# P10_EX-Headers.net
KiCad netlist of a schematic drawn in Altium Designer
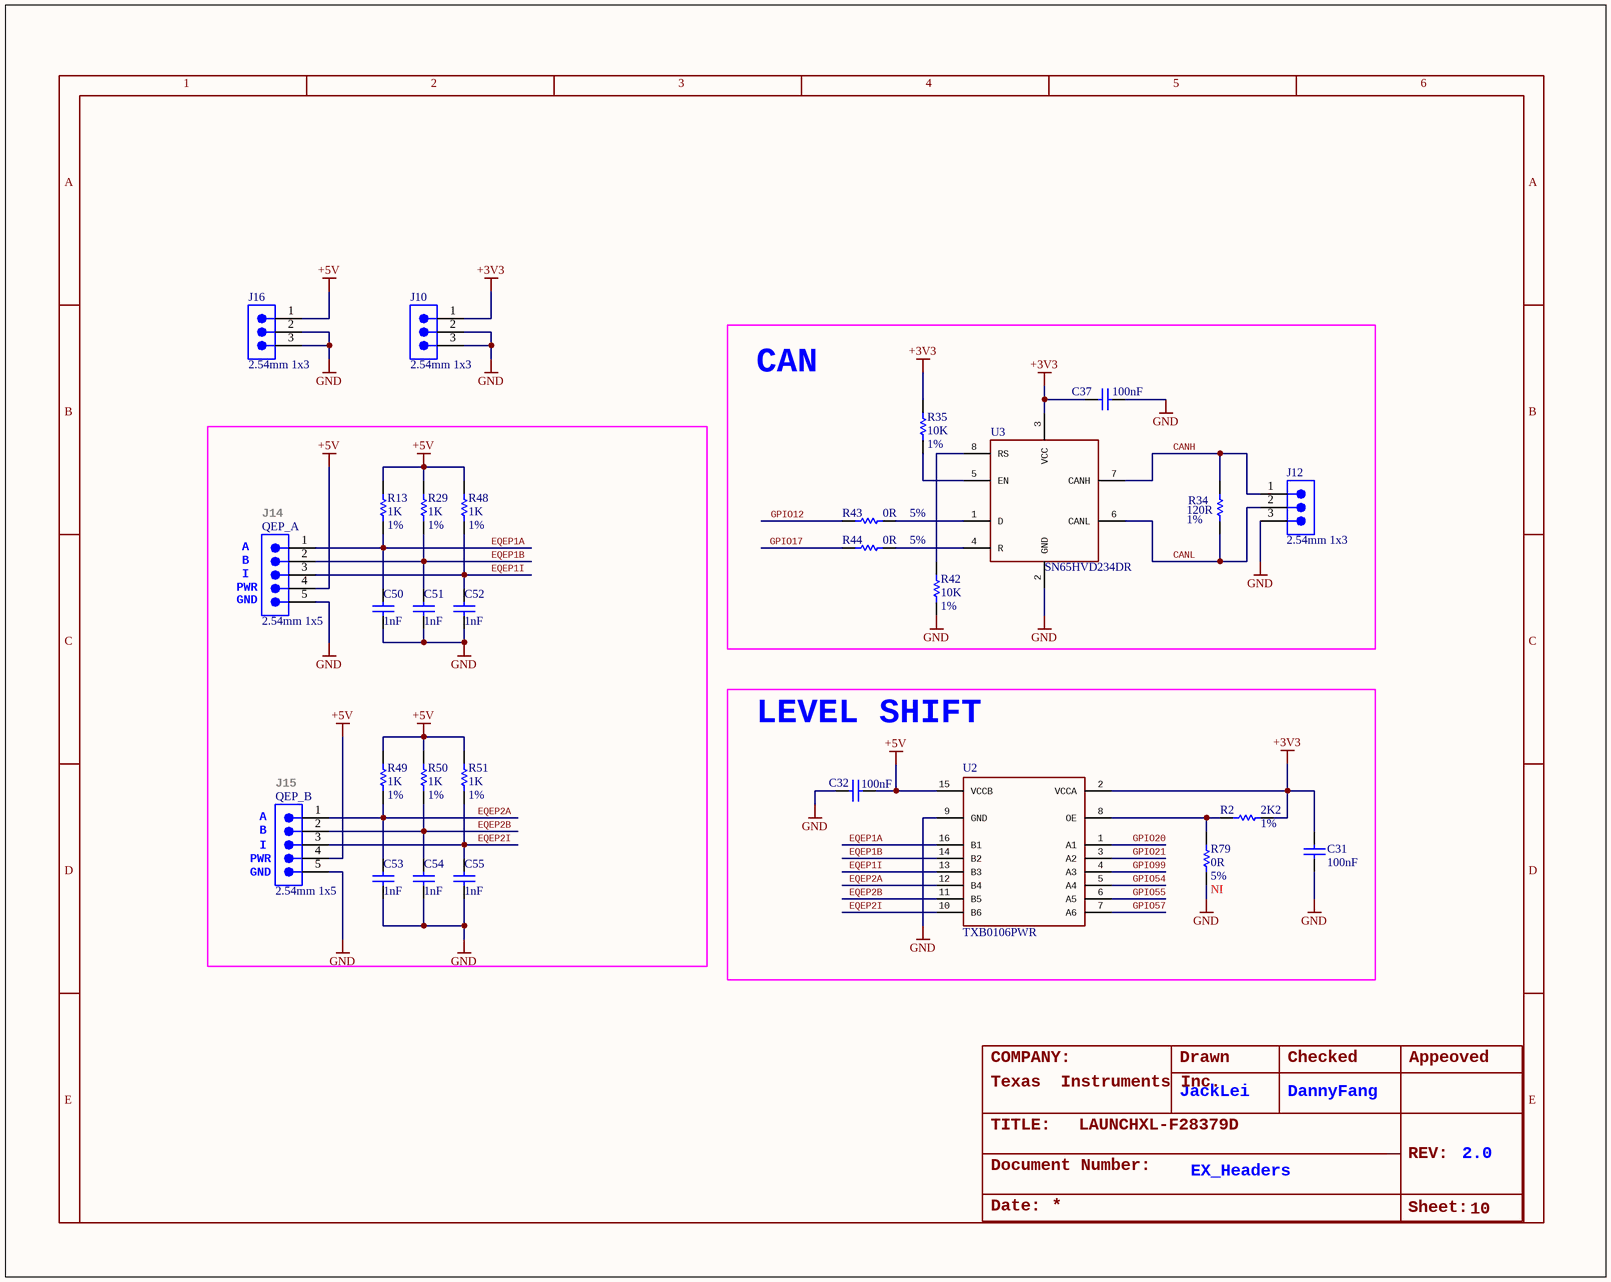
[diagram p0: P10_EX-Headers.SchDoc]

(export (version "E")
  (design (tool "Eeschema 10.0.6"))
  (components
    (comp (ref "C31")
      (value "100nF")
      (footprint "C0402")
      (description "CAP,100NF(0.1uf),+/-10%,X5R,10V,SMD0402")
      (fields
        (field (name "MANUFACTURER") "MURATA")
        (field (name "MANUFACTURER PART NUMBER") "GRM155R61A104KA01D")
      )
      (libsource (lib "Embest") (part "C"))
    )
    (comp (ref "C32")
      (value "100nF")
      (footprint "C0402")
      (description "CAP,100NF(0.1uf),+/-10%,X5R,10V,SMD0402")
      (fields
        (field (name "MANUFACTURER") "MURATA")
        (field (name "MANUFACTURER PART NUMBER") "GRM155R61A104KA01D")
      )
      (libsource (lib "Embest") (part "C"))
    )
    (comp (ref "C37")
      (value "100nF")
      (footprint "C0402")
      (description "CAP,100NF(0.1uf),+/-10%,X5R,10V,SMD0402")
      (fields
        (field (name "MANUFACTURER") "MURATA")
        (field (name "MANUFACTURER PART NUMBER") "GRM155R61A104KA01D")
      )
      (libsource (lib "Embest") (part "C"))
    )
    (comp (ref "C50")
      (value "1nF")
      (footprint "C0402")
      (description "CAP,1NF,+/-10%,X7R,50V,SMD0402")
      (fields
        (field (name "MANUFACTURER") "MURATA")
        (field (name "MANUFACTURER PART NUMBER") "GRM155R71H102KA01D")
      )
      (libsource (lib "Embest") (part "C"))
    )
    (comp (ref "C51")
      (value "1nF")
      (footprint "C0402")
      (description "CAP,1NF,+/-10%,X7R,50V,SMD0402")
      (fields
        (field (name "MANUFACTURER") "MURATA")
        (field (name "MANUFACTURER PART NUMBER") "GRM155R71H102KA01D")
      )
      (libsource (lib "Embest") (part "C"))
    )
    (comp (ref "C52")
      (value "1nF")
      (footprint "C0402")
      (description "CAP,1NF,+/-10%,X7R,50V,SMD0402")
      (fields
        (field (name "MANUFACTURER") "MURATA")
        (field (name "MANUFACTURER PART NUMBER") "GRM155R71H102KA01D")
      )
      (libsource (lib "Embest") (part "C"))
    )
    (comp (ref "C53")
      (value "1nF")
      (footprint "C0402")
      (description "CAP,1NF,+/-10%,X7R,50V,SMD0402")
      (fields
        (field (name "MANUFACTURER") "MURATA")
        (field (name "MANUFACTURER PART NUMBER") "GRM155R71H102KA01D")
      )
      (libsource (lib "Embest") (part "C"))
    )
    (comp (ref "C54")
      (value "1nF")
      (footprint "C0402")
      (description "CAP,1NF,+/-10%,X7R,50V,SMD0402")
      (fields
        (field (name "MANUFACTURER") "MURATA")
        (field (name "MANUFACTURER PART NUMBER") "GRM155R71H102KA01D")
      )
      (libsource (lib "Embest") (part "C"))
    )
    (comp (ref "C55")
      (value "1nF")
      (footprint "C0402")
      (description "CAP,1NF,+/-10%,X7R,50V,SMD0402")
      (fields
        (field (name "MANUFACTURER") "MURATA")
        (field (name "MANUFACTURER PART NUMBER") "GRM155R71H102KA01D")
      )
      (libsource (lib "Embest") (part "C"))
    )
    (comp (ref "J10")
      (value "2.54mm 1x3")
      (footprint "HDRV3W64P254_1X3_762X250X850P")
      (fields
        (field (name "MANUFACTURER") "CHIN-BAN")
        (field (name "MANUFACTURER PART NUMBER") "P6E03A-602530-B1")
      )
      (libsource (lib "") (part "SIP3_1"))
    )
    (comp (ref "J12")
      (value "2.54mm 1x3")
      (footprint "HDRV3W64P254_1X3_762X250X850P")
      (fields
        (field (name "MANUFACTURER") "CHIN-BAN")
        (field (name "MANUFACTURER PART NUMBER") "P6E03A-602530-B1")
      )
      (libsource (lib "Embest") (part "SIP3"))
    )
    (comp (ref "J16")
      (value "2.54mm 1x3")
      (footprint "HDRV3W64P254_1X3_762X250X850P")
      (fields
        (field (name "MANUFACTURER") "CHIN-BAN")
        (field (name "MANUFACTURER PART NUMBER") "P6E03A-602530-B1")
      )
      (libsource (lib "") (part "SIP3_1"))
    )
    (comp (ref "QEP_A")
      (value "2.54mm 1x5")
      (footprint "HDRV5W64P254_1X5_1270X250X850P")
      (description "Connector,Pin Header,Straight,Male,1x5Pin,2.54MM pitch,6.06,3.00,Gold Flash 1u, black,DIP")
      (fields
        (field (name "MANUFACTURER") "TOWNES")
        (field (name "MANUFACTURER PART NUMBER") "P101-1*05SGF-116A-NX")
      )
      (libsource (lib "Embest") (part "SIP5"))
    )
    (comp (ref "QEP_B")
      (value "2.54mm 1x5")
      (footprint "HDRV5W64P254_1X5_1270X250X850P")
      (description "Connector,Pin Header,Straight,Male,1x5Pin,2.54MM pitch,6.06,3.00,Gold Flash 1u, black,DIP")
      (fields
        (field (name "MANUFACTURER") "TOWNES")
        (field (name "MANUFACTURER PART NUMBER") "P101-1*05SGF-116A-NX")
      )
      (libsource (lib "Embest") (part "SIP5"))
    )
    (comp (ref "R2")
      (value "2K2")
      (footprint "R0402")
      (description "RES,2K2,+/-1%,1/16W,SMD0402")
      (fields
        (field (name "RATING") "1%")
        (field (name "MANUFACTURER") "YAGEO")
        (field (name "MANUFACTURER PART NUMBER") "RC0402FR-072K2L")
      )
      (libsource (lib "Embest") (part "R"))
    )
    (comp (ref "R13")
      (value "1K")
      (footprint "R0402")
      (description "RES,1K,+/-1%,1/16W,SMD0402")
      (fields
        (field (name "RATING") "1%")
        (field (name "MANUFACTURER") "YAGEO")
        (field (name "MANUFACTURER PART NUMBER") "RC0402FR-071KL")
      )
      (libsource (lib "Embest") (part "R"))
    )
    (comp (ref "R29")
      (value "1K")
      (footprint "R0402")
      (description "RES,1K,+/-1%,1/16W,SMD0402")
      (fields
        (field (name "RATING") "1%")
        (field (name "MANUFACTURER") "YAGEO")
        (field (name "MANUFACTURER PART NUMBER") "RC0402FR-071KL")
      )
      (libsource (lib "Embest") (part "R"))
    )
    (comp (ref "R34")
      (value "120R")
      (footprint "R0603")
      (description "RES,120R,+/-1%,1/10W,SMD0603")
      (fields
        (field (name "RATING") "1%")
        (field (name "MANUFACTURER") "YAGEO")
        (field (name "MANUFACTURER PART NUMBER") "RC0603FR-07120RL")
      )
      (libsource (lib "Embest") (part "R"))
    )
    (comp (ref "R35")
      (value "10K")
      (footprint "R0402")
      (description "RES,10K,+/-1%,1/16W,SMD0402")
      (fields
        (field (name "RATING") "1%")
        (field (name "MANUFACTURER") "YAGEO")
        (field (name "MANUFACTURER PART NUMBER") "RC0402FR-0710KL")
      )
      (libsource (lib "Embest") (part "R"))
    )
    (comp (ref "R42")
      (value "10K")
      (footprint "R0402")
      (description "RES,10K,+/-1%,1/16W,SMD0402")
      (fields
        (field (name "RATING") "1%")
        (field (name "MANUFACTURER") "YAGEO")
        (field (name "MANUFACTURER PART NUMBER") "RC0402FR-0710KL")
      )
      (libsource (lib "Embest") (part "R"))
    )
    (comp (ref "R43")
      (value "0R")
      (footprint "R0402")
      (description "RES,0R,+/-5%,1/16W,SMD0402")
      (fields
        (field (name "RATING") "5%")
        (field (name "MANUFACTURER") "YAGEO")
        (field (name "MANUFACTURER PART NUMBER") "RC0402JR-070RL")
      )
      (libsource (lib "Embest") (part "R"))
    )
    (comp (ref "R44")
      (value "0R")
      (footprint "R0402")
      (description "RES,0R,+/-5%,1/16W,SMD0402")
      (fields
        (field (name "RATING") "5%")
        (field (name "MANUFACTURER") "YAGEO")
        (field (name "MANUFACTURER PART NUMBER") "RC0402JR-070RL")
      )
      (libsource (lib "Embest") (part "R"))
    )
    (comp (ref "R48")
      (value "1K")
      (footprint "R0402")
      (description "RES,1K,+/-1%,1/16W,SMD0402")
      (fields
        (field (name "RATING") "1%")
        (field (name "MANUFACTURER") "YAGEO")
        (field (name "MANUFACTURER PART NUMBER") "RC0402FR-071KL")
      )
      (libsource (lib "Embest") (part "R"))
    )
    (comp (ref "R49")
      (value "1K")
      (footprint "R0402")
      (description "RES,1K,+/-1%,1/16W,SMD0402")
      (fields
        (field (name "RATING") "1%")
        (field (name "MANUFACTURER") "YAGEO")
        (field (name "MANUFACTURER PART NUMBER") "RC0402FR-071KL")
      )
      (libsource (lib "Embest") (part "R"))
    )
    (comp (ref "R50")
      (value "1K")
      (footprint "R0402")
      (description "RES,1K,+/-1%,1/16W,SMD0402")
      (fields
        (field (name "RATING") "1%")
        (field (name "MANUFACTURER") "YAGEO")
        (field (name "MANUFACTURER PART NUMBER") "RC0402FR-071KL")
      )
      (libsource (lib "Embest") (part "R"))
    )
    (comp (ref "R51")
      (value "1K")
      (footprint "R0402")
      (description "RES,1K,+/-1%,1/16W,SMD0402")
      (fields
        (field (name "RATING") "1%")
        (field (name "MANUFACTURER") "YAGEO")
        (field (name "MANUFACTURER PART NUMBER") "RC0402FR-071KL")
      )
      (libsource (lib "Embest") (part "R"))
    )
    (comp (ref "R79")
      (value "0R")
      (footprint "R0603")
      (description "RES,0R,+/-5%,1/10W,SMD0603")
      (fields
        (field (name "RATING") "5%")
        (field (name "ASSY") "NI")
        (field (name "MANUFACTURER") "YAGEO")
        (field (name "MANUFACTURER PART NUMBER") "RC0603JR-070RL")
      )
      (libsource (lib "Embest") (part "R"))
    )
    (comp (ref "U2")
      (value "TXB0106PWR")
      (footprint "TSSOP65P640X120-16N")
      (fields (field (name "MANUFACTURER") "TI"))
      (libsource (lib "Embest") (part "TXB0106PWR"))
    )
    (comp (ref "U3")
      (value "SN65HVD234DR")
      (footprint "SOIC127P600X175-8N")
      (description "IC CAN TRANSCEIVER 3.3V 8-SOIC")
      (fields (field (name "MANUFACTURER") "TI"))
      (libsource (lib "Embest") (part "SN65HVD234D"))
    )
  )
  (nets
    (net (code "1") (name "+3V3") (class "Default")
      (node (ref "C31") (pin "1") (pinfunction "1_1") (pintype "passive"))
      (node (ref "C37") (pin "2") (pinfunction "2_2") (pintype "passive"))
      (node (ref "J10") (pin "1") (pinfunction "1_1") (pintype "passive"))
      (node (ref "R2") (pin "1") (pinfunction "1_1") (pintype "passive"))
      (node (ref "R35") (pin "2") (pinfunction "2_2") (pintype "passive"))
      (node (ref "U2") (pin "2") (pinfunction "VCCA_2") (pintype "passive"))
      (node (ref "U3") (pin "3") (pinfunction "VCC_3") (pintype "passive"))
    )
    (net (code "2") (name "+5V") (class "Default")
      (node (ref "C32") (pin "2") (pinfunction "2_2") (pintype "passive"))
      (node (ref "J16") (pin "1") (pinfunction "1_1") (pintype "passive"))
      (node (ref "QEP_A") (pin "4") (pinfunction "4_4") (pintype "passive"))
      (node (ref "QEP_B") (pin "4") (pinfunction "4_4") (pintype "passive"))
      (node (ref "R13") (pin "1") (pinfunction "1_1") (pintype "passive"))
      (node (ref "R29") (pin "1") (pinfunction "1_1") (pintype "passive"))
      (node (ref "R48") (pin "1") (pinfunction "1_1") (pintype "passive"))
      (node (ref "R49") (pin "1") (pinfunction "1_1") (pintype "passive"))
      (node (ref "R50") (pin "1") (pinfunction "1_1") (pintype "passive"))
      (node (ref "R51") (pin "1") (pinfunction "1_1") (pintype "passive"))
      (node (ref "U2") (pin "15") (pinfunction "VCCB_15") (pintype "passive"))
    )
    (net (code "3") (name "/CANH") (class "Default")
      (node (ref "J12") (pin "1") (pinfunction "1_1") (pintype "passive"))
      (node (ref "R34") (pin "2") (pinfunction "2_2") (pintype "passive"))
      (node (ref "U3") (pin "7") (pinfunction "CANH_7") (pintype "passive"))
    )
    (net (code "4") (name "/CANL") (class "Default")
      (node (ref "J12") (pin "2") (pinfunction "2_2") (pintype "passive"))
      (node (ref "R34") (pin "1") (pinfunction "1_1") (pintype "passive"))
      (node (ref "U3") (pin "6") (pinfunction "CANL_6") (pintype "passive"))
    )
    (net (code "5") (name "/EQEP1A") (class "Default")
      (node (ref "C50") (pin "2") (pinfunction "2_2") (pintype "passive"))
      (node (ref "QEP_A") (pin "1") (pinfunction "1_1") (pintype "passive"))
      (node (ref "R13") (pin "2") (pinfunction "2_2") (pintype "passive"))
      (node (ref "U2") (pin "16") (pinfunction "B1_16") (pintype "passive"))
    )
    (net (code "6") (name "/EQEP1B") (class "Default")
      (node (ref "C51") (pin "2") (pinfunction "2_2") (pintype "passive"))
      (node (ref "QEP_A") (pin "2") (pinfunction "2_2") (pintype "passive"))
      (node (ref "R29") (pin "2") (pinfunction "2_2") (pintype "passive"))
      (node (ref "U2") (pin "14") (pinfunction "B2_14") (pintype "passive"))
    )
    (net (code "7") (name "/EQEP1I") (class "Default")
      (node (ref "C52") (pin "2") (pinfunction "2_2") (pintype "passive"))
      (node (ref "QEP_A") (pin "3") (pinfunction "3_3") (pintype "passive"))
      (node (ref "R48") (pin "2") (pinfunction "2_2") (pintype "passive"))
      (node (ref "U2") (pin "13") (pinfunction "B3_13") (pintype "passive"))
    )
    (net (code "8") (name "/EQEP2A") (class "Default")
      (node (ref "C53") (pin "2") (pinfunction "2_2") (pintype "passive"))
      (node (ref "QEP_B") (pin "1") (pinfunction "1_1") (pintype "passive"))
      (node (ref "R49") (pin "2") (pinfunction "2_2") (pintype "passive"))
      (node (ref "U2") (pin "12") (pinfunction "B4_12") (pintype "passive"))
    )
    (net (code "9") (name "/EQEP2B") (class "Default")
      (node (ref "C54") (pin "2") (pinfunction "2_2") (pintype "passive"))
      (node (ref "QEP_B") (pin "2") (pinfunction "2_2") (pintype "passive"))
      (node (ref "R50") (pin "2") (pinfunction "2_2") (pintype "passive"))
      (node (ref "U2") (pin "11") (pinfunction "B5_11") (pintype "passive"))
    )
    (net (code "10") (name "/EQEP2I") (class "Default")
      (node (ref "C55") (pin "2") (pinfunction "2_2") (pintype "passive"))
      (node (ref "QEP_B") (pin "3") (pinfunction "3_3") (pintype "passive"))
      (node (ref "R51") (pin "2") (pinfunction "2_2") (pintype "passive"))
      (node (ref "U2") (pin "10") (pinfunction "B6_10") (pintype "passive"))
    )
    (net (code "11") (name "/GPIO12") (class "Default")
      (node (ref "R43") (pin "2") (pinfunction "2_2") (pintype "passive"))
    )
    (net (code "12") (name "/GPIO17") (class "Default")
      (node (ref "R44") (pin "2") (pinfunction "2_2") (pintype "passive"))
    )
    (net (code "13") (name "/GPIO20") (class "Default")
      (node (ref "U2") (pin "1") (pinfunction "A1_1") (pintype "passive"))
    )
    (net (code "14") (name "/GPIO21") (class "Default")
      (node (ref "U2") (pin "3") (pinfunction "A2_3") (pintype "passive"))
    )
    (net (code "15") (name "/GPIO54") (class "Default")
      (node (ref "U2") (pin "5") (pinfunction "A4_5") (pintype "passive"))
    )
    (net (code "16") (name "/GPIO55") (class "Default")
      (node (ref "U2") (pin "6") (pinfunction "A5_6") (pintype "passive"))
    )
    (net (code "17") (name "/GPIO57") (class "Default")
      (node (ref "U2") (pin "7") (pinfunction "A6_7") (pintype "passive"))
    )
    (net (code "18") (name "/GPIO99") (class "Default")
      (node (ref "U2") (pin "4") (pinfunction "A3_4") (pintype "passive"))
    )
    (net (code "19") (name "GND") (class "Default")
      (node (ref "C31") (pin "2") (pinfunction "2_2") (pintype "passive"))
      (node (ref "C32") (pin "1") (pinfunction "1_1") (pintype "passive"))
      (node (ref "C37") (pin "1") (pinfunction "1_1") (pintype "passive"))
      (node (ref "C50") (pin "1") (pinfunction "1_1") (pintype "passive"))
      (node (ref "C51") (pin "1") (pinfunction "1_1") (pintype "passive"))
      (node (ref "C52") (pin "1") (pinfunction "1_1") (pintype "passive"))
      (node (ref "C53") (pin "1") (pinfunction "1_1") (pintype "passive"))
      (node (ref "C54") (pin "1") (pinfunction "1_1") (pintype "passive"))
      (node (ref "C55") (pin "1") (pinfunction "1_1") (pintype "passive"))
      (node (ref "J10") (pin "2") (pinfunction "2_2") (pintype "passive"))
      (node (ref "J10") (pin "3") (pinfunction "3_3") (pintype "passive"))
      (node (ref "J12") (pin "3") (pinfunction "3_3") (pintype "passive"))
      (node (ref "J16") (pin "2") (pinfunction "2_2") (pintype "passive"))
      (node (ref "J16") (pin "3") (pinfunction "3_3") (pintype "passive"))
      (node (ref "QEP_A") (pin "5") (pinfunction "5_5") (pintype "passive"))
      (node (ref "QEP_B") (pin "5") (pinfunction "5_5") (pintype "passive"))
      (node (ref "R42") (pin "2") (pinfunction "2_2") (pintype "passive"))
      (node (ref "R79") (pin "2") (pinfunction "2_2") (pintype "passive"))
      (node (ref "U2") (pin "9") (pinfunction "GND_9") (pintype "passive"))
      (node (ref "U3") (pin "2") (pinfunction "GND_2") (pintype "passive"))
    )
    (net (code "20") (name "Net-(U2-OE)") (class "Default")
      (node (ref "R2") (pin "2") (pinfunction "2_2") (pintype "passive"))
      (node (ref "R79") (pin "1") (pinfunction "1_1") (pintype "passive"))
      (node (ref "U2") (pin "8") (pinfunction "OE_8") (pintype "passive"))
    )
    (net (code "21") (name "Net-(U3-D)") (class "Default")
      (node (ref "R43") (pin "1") (pinfunction "1_1") (pintype "passive"))
      (node (ref "U3") (pin "1") (pinfunction "D_1") (pintype "passive"))
    )
    (net (code "22") (name "Net-(U3-EN)") (class "Default")
      (node (ref "R35") (pin "1") (pinfunction "1_1") (pintype "passive"))
      (node (ref "U3") (pin "5") (pinfunction "EN_5") (pintype "passive"))
    )
    (net (code "23") (name "Net-(U3-R)") (class "Default")
      (node (ref "R44") (pin "1") (pinfunction "1_1") (pintype "passive"))
      (node (ref "U3") (pin "4") (pinfunction "R_4") (pintype "passive"))
    )
    (net (code "24") (name "Net-(U3-RS)") (class "Default")
      (node (ref "R42") (pin "1") (pinfunction "1_1") (pintype "passive"))
      (node (ref "U3") (pin "8") (pinfunction "RS_8") (pintype "passive"))
    )
  )
)
